# POKERKIDV1TESTBOARD.net
KiCad netlist of a schematic drawn in Altium Designer
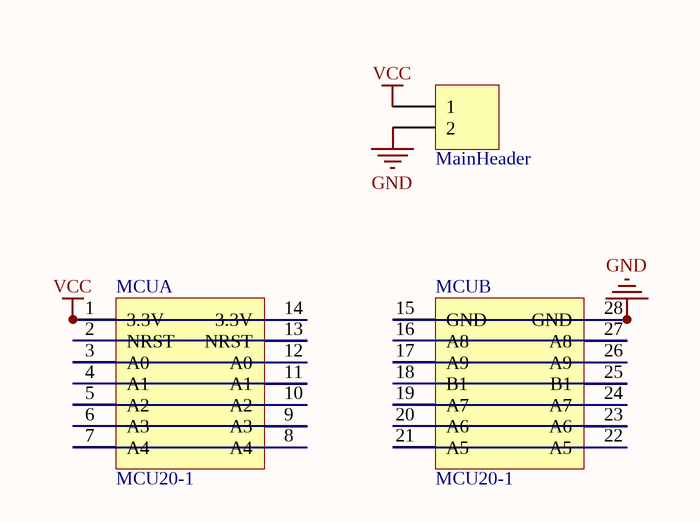
[diagram p0: POKERKIDV1TESTBOARD.SchDoc]

(export (version "E")
  (design (tool "Eeschema 10.0.6"))
  (components
    (comp (ref "MainHeader")
      (value "691312510002")
      (footprint "691312510002")
      (description "WR-TBL Terminal Blocks Serie 312 – 5.08 mm")
      (fields
        (field (name "MANUFACTURER") "Würth Elektronik eiSos GmbH")
        (field (name "CREATED BY") "Karrer Zheng")
      )
      (libsource (lib "WE_WR-TBL_Pluggable System_5.08 mm_rev15basdasd") (part "691312510002"))
    )
    (comp (ref "MCU") (value "MCU20-1") (footprint "MCU20-1") (libsource (lib "Aryalib") (part "MCU20-1")))
  )
  (nets
    (net (code "1") (name "GND") (class "Default")
      (node (ref "MCU") (pin "15") (pinfunction "GND_15") (pintype "passive"))
      (node (ref "MCU") (pin "28") (pinfunction "GND_28") (pintype "passive"))
      (node (ref "MainHeader") (pin "2") (pinfunction "2_2") (pintype "passive"))
    )
    (net (code "2") (name "Net-(MCUA-A0-Pad12)") (class "Default")
      (node (ref "MCU") (pin "12") (pinfunction "A0_12") (pintype "passive"))
      (node (ref "MCU") (pin "3") (pinfunction "A0_3") (pintype "passive"))
    )
    (net (code "3") (name "Net-(MCUA-A1-Pad11)") (class "Default")
      (node (ref "MCU") (pin "11") (pinfunction "A1_11") (pintype "passive"))
      (node (ref "MCU") (pin "4") (pinfunction "A1_4") (pintype "passive"))
    )
    (net (code "4") (name "Net-(MCUA-A2-Pad10)") (class "Default")
      (node (ref "MCU") (pin "10") (pinfunction "A2_10") (pintype "passive"))
      (node (ref "MCU") (pin "5") (pinfunction "A2_5") (pintype "passive"))
    )
    (net (code "5") (name "Net-(MCUA-A3-Pad6)") (class "Default")
      (node (ref "MCU") (pin "6") (pinfunction "A3_6") (pintype "passive"))
      (node (ref "MCU") (pin "9") (pinfunction "A3_9") (pintype "passive"))
    )
    (net (code "6") (name "Net-(MCUA-A4-Pad7)") (class "Default")
      (node (ref "MCU") (pin "7") (pinfunction "A4_7") (pintype "passive"))
      (node (ref "MCU") (pin "8") (pinfunction "A4_8") (pintype "passive"))
    )
    (net (code "7") (name "Net-(MCUA-NRST-Pad13)") (class "Default")
      (node (ref "MCU") (pin "13") (pinfunction "NRST_13") (pintype "passive"))
      (node (ref "MCU") (pin "2") (pinfunction "NRST_2") (pintype "passive"))
    )
    (net (code "8") (name "Net-(MCUB-A5-Pad21)") (class "Default")
      (node (ref "MCU") (pin "21") (pinfunction "A5_21") (pintype "passive"))
      (node (ref "MCU") (pin "22") (pinfunction "A5_22") (pintype "passive"))
    )
    (net (code "9") (name "Net-(MCUB-A6-Pad20)") (class "Default")
      (node (ref "MCU") (pin "20") (pinfunction "A6_20") (pintype "passive"))
      (node (ref "MCU") (pin "23") (pinfunction "A6_23") (pintype "passive"))
    )
    (net (code "10") (name "Net-(MCUB-A7-Pad19)") (class "Default")
      (node (ref "MCU") (pin "19") (pinfunction "A7_19") (pintype "passive"))
      (node (ref "MCU") (pin "24") (pinfunction "A7_24") (pintype "passive"))
    )
    (net (code "11") (name "Net-(MCUB-A8-Pad16)") (class "Default")
      (node (ref "MCU") (pin "16") (pinfunction "A8_16") (pintype "passive"))
      (node (ref "MCU") (pin "27") (pinfunction "A8_27") (pintype "passive"))
    )
    (net (code "12") (name "Net-(MCUB-A9-Pad17)") (class "Default")
      (node (ref "MCU") (pin "17") (pinfunction "A9_17") (pintype "passive"))
      (node (ref "MCU") (pin "26") (pinfunction "A9_26") (pintype "passive"))
    )
    (net (code "13") (name "Net-(MCUB-B1-Pad18)") (class "Default")
      (node (ref "MCU") (pin "18") (pinfunction "B1_18") (pintype "passive"))
      (node (ref "MCU") (pin "25") (pinfunction "B1_25") (pintype "passive"))
    )
    (net (code "14") (name "VCC") (class "Default")
      (node (ref "MCU") (pin "1") (pinfunction "3.3V_1") (pintype "passive"))
      (node (ref "MCU") (pin "14") (pinfunction "3.3V_14") (pintype "passive"))
      (node (ref "MainHeader") (pin "1") (pinfunction "1_1") (pintype "passive"))
    )
  )
)
